# 4G.net
KiCad netlist of a schematic drawn in Altium Designer
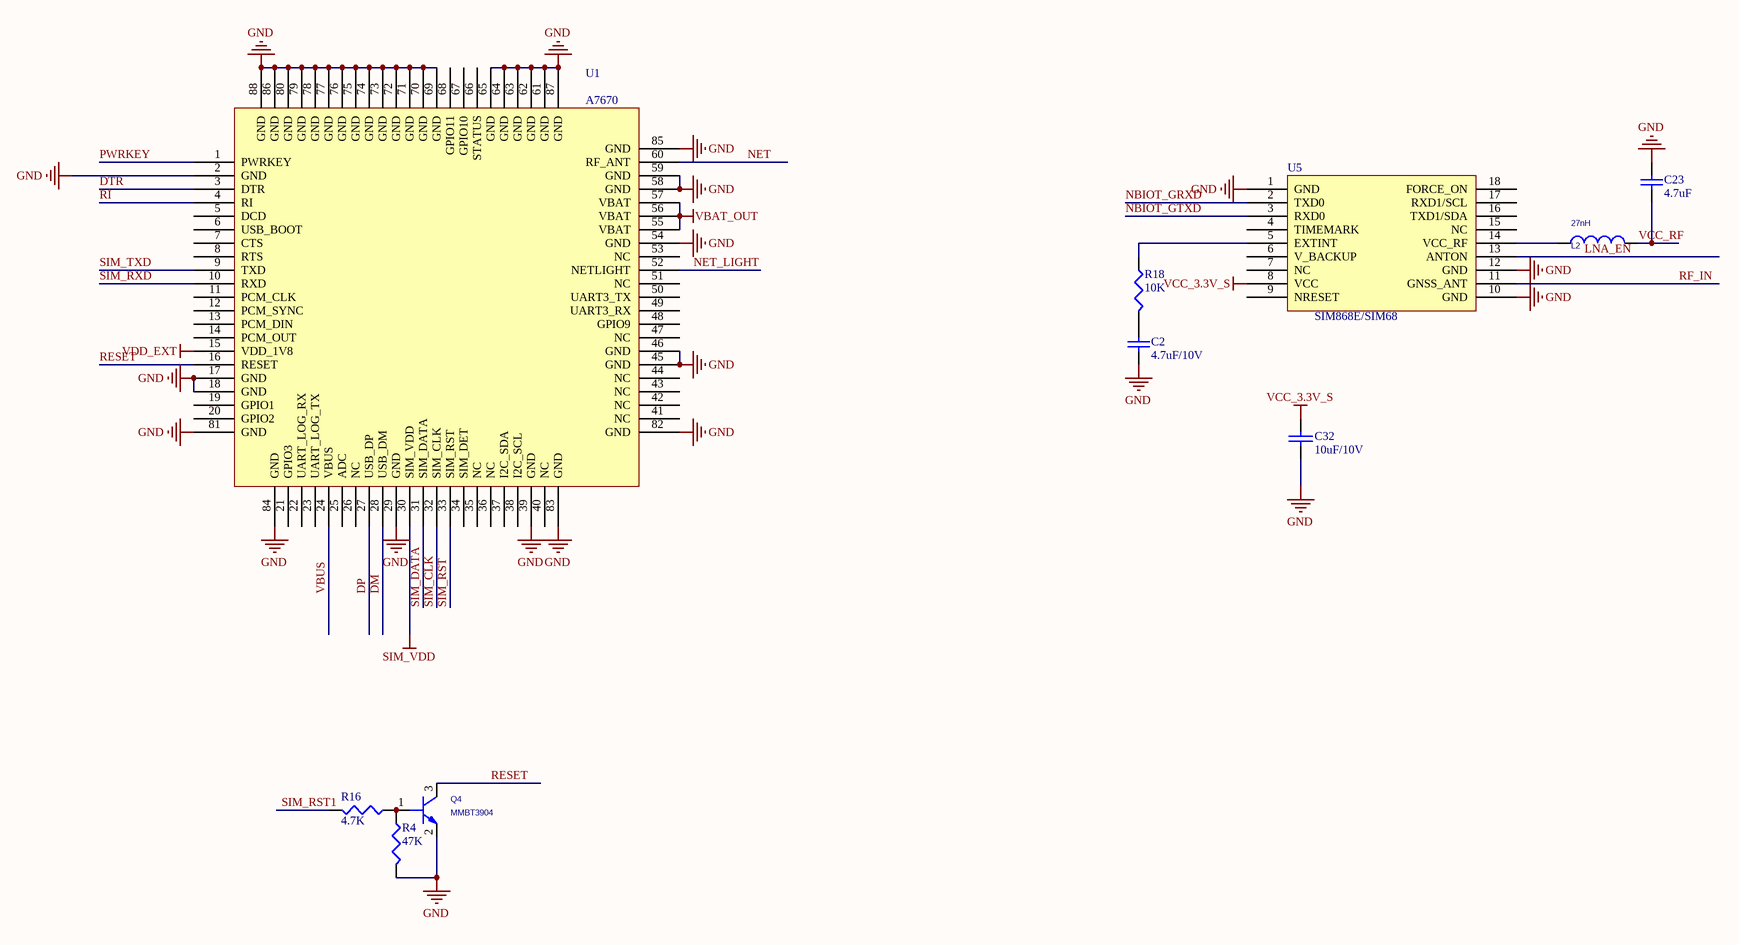
[diagram p0: 4G.SchDoc]

(export (version "E")
  (design (tool "Eeschema 10.0.6"))
  (components
    (comp (ref "C2")
      (value "4.7uF/10V")
      (footprint "0402c")
      (description "Capacitor")
      (fields (field (name "PUBLISHER") "Altium Limited"))
      (libsource (lib "Miscellaneous Devices") (part "Cap"))
    )
    (comp (ref "C23")
      (value "4.7uF")
      (footprint "0402c")
      (description "Capacitor")
      (fields (field (name "PUBLISHER") "Altium Limited"))
      (libsource (lib "Miscellaneous Devices") (part "Cap"))
    )
    (comp (ref "C32")
      (value "10uF/10V")
      (footprint "0402C")
      (description "Capacitor")
      (libsource (lib "ZWLIntegrated_Library") (part "CAP"))
    )
    (comp (ref "L2") (value "27nH") (footprint "0402R") (libsource (lib "*") (part "INDUCTOR_1")))
    (comp (ref "Q4") (value "MMBT3904") (footprint "SOT23-3") (libsource (lib "*") (part "2N1069_1")))
    (comp (ref "R4")
      (value "47K")
      (footprint "0402R")
      (libsource (lib "ZWLIntegrated_Library") (part "RES1"))
    )
    (comp (ref "R16")
      (value "4.7K")
      (footprint "0402R")
      (libsource (lib "ZWLIntegrated_Library") (part "RES1"))
    )
    (comp (ref "R18")
      (value "10K")
      (footprint "0402R")
      (libsource (lib "ZWLIntegrated_Library") (part "RES1"))
    )
    (comp (ref "U1") (value "A7670") (footprint "A7670") (libsource (lib "stm32") (part "A7670")))
    (comp (ref "U5") (value "SIM868E/SIM68") (footprint "SIM68MB") (libsource (lib "stm32") (part "SIM68MB")))
  )
  (nets
    (net (code "1") (name "/DM") (class "Default")
      (node (ref "U1") (pin "28") (pinfunction "USB_DM_28") (pintype "passive"))
    )
    (net (code "2") (name "/DP") (class "Default")
      (node (ref "U1") (pin "27") (pinfunction "USB_DP_27") (pintype "passive"))
    )
    (net (code "3") (name "/DTR") (class "Default")
      (node (ref "U1") (pin "3") (pinfunction "DTR_3") (pintype "passive"))
    )
    (net (code "4") (name "/LNA_EN") (class "Default")
      (node (ref "U5") (pin "13") (pinfunction "ANTON_13") (pintype "passive"))
    )
    (net (code "5") (name "/NBIOT_GRXD") (class "Default")
      (node (ref "U5") (pin "2") (pinfunction "TXD0_2") (pintype "passive"))
    )
    (net (code "6") (name "/NBIOT_GTXD") (class "Default")
      (node (ref "U5") (pin "3") (pinfunction "RXD0_3") (pintype "passive"))
    )
    (net (code "7") (name "/NET") (class "Default")
      (node (ref "U1") (pin "60") (pinfunction "RF_ANT_60") (pintype "passive"))
    )
    (net (code "8") (name "/NET_LIGHT") (class "Default")
      (node (ref "U1") (pin "52") (pinfunction "NETLIGHT_52") (pintype "passive"))
    )
    (net (code "9") (name "/PWRKEY") (class "Default")
      (node (ref "U1") (pin "1") (pinfunction "PWRKEY_1") (pintype "passive"))
    )
    (net (code "10") (name "/RESET") (class "Default")
      (node (ref "Q4") (pin "3") (pinfunction "C_3") (pintype "passive"))
      (node (ref "U1") (pin "16") (pinfunction "RESET_16") (pintype "passive"))
    )
    (net (code "11") (name "/RF_IN") (class "Default")
      (node (ref "U5") (pin "11") (pinfunction "GNSS_ANT_11") (pintype "passive"))
    )
    (net (code "12") (name "/RI") (class "Default")
      (node (ref "U1") (pin "4") (pinfunction "RI_4") (pintype "passive"))
    )
    (net (code "13") (name "/SIM_CLK") (class "Default")
      (node (ref "U1") (pin "32") (pinfunction "SIM_CLK_32") (pintype "passive"))
    )
    (net (code "14") (name "/SIM_DATA") (class "Default")
      (node (ref "U1") (pin "31") (pinfunction "SIM_DATA_31") (pintype "passive"))
    )
    (net (code "15") (name "/SIM_RST") (class "Default")
      (node (ref "U1") (pin "33") (pinfunction "SIM_RST_33") (pintype "passive"))
    )
    (net (code "16") (name "/SIM_RST1") (class "Default")
      (node (ref "R16") (pin "2") (pinfunction "2_2") (pintype "passive"))
    )
    (net (code "17") (name "/SIM_RXD") (class "Default")
      (node (ref "U1") (pin "10") (pinfunction "RXD_10") (pintype "passive"))
    )
    (net (code "18") (name "/SIM_TXD") (class "Default")
      (node (ref "U1") (pin "9") (pinfunction "TXD_9") (pintype "passive"))
    )
    (net (code "19") (name "/VBUS") (class "Default")
      (node (ref "U1") (pin "24") (pinfunction "VBUS_24") (pintype "passive"))
    )
    (net (code "20") (name "/VCC_RF") (class "Default")
      (node (ref "C23") (pin "2") (pinfunction "2_2") (pintype "passive"))
      (node (ref "L2") (pin "2") (pinfunction "2_2") (pintype "passive"))
    )
    (net (code "21") (name "GND") (class "Default")
      (node (ref "C2") (pin "1") (pinfunction "1_1") (pintype "passive"))
      (node (ref "C23") (pin "1") (pinfunction "1_1") (pintype "passive"))
      (node (ref "C32") (pin "1") (pinfunction "1_1") (pintype "passive"))
      (node (ref "Q4") (pin "2") (pinfunction "E_2") (pintype "passive"))
      (node (ref "R4") (pin "2") (pinfunction "2_2") (pintype "passive"))
      (node (ref "U1") (pin "17") (pinfunction "GND_17") (pintype "passive"))
      (node (ref "U1") (pin "18") (pinfunction "GND_18") (pintype "passive"))
      (node (ref "U1") (pin "2") (pinfunction "GND_2") (pintype "passive"))
      (node (ref "U1") (pin "29") (pinfunction "GND_29") (pintype "passive"))
      (node (ref "U1") (pin "39") (pinfunction "GND_39") (pintype "passive"))
      (node (ref "U1") (pin "45") (pinfunction "GND_45") (pintype "passive"))
      (node (ref "U1") (pin "46") (pinfunction "GND_46") (pintype "passive"))
      (node (ref "U1") (pin "54") (pinfunction "GND_54") (pintype "passive"))
      (node (ref "U1") (pin "58") (pinfunction "GND_58") (pintype "passive"))
      (node (ref "U1") (pin "59") (pinfunction "GND_59") (pintype "passive"))
      (node (ref "U1") (pin "61") (pinfunction "GND_61") (pintype "passive"))
      (node (ref "U1") (pin "62") (pinfunction "GND_62") (pintype "passive"))
      (node (ref "U1") (pin "63") (pinfunction "GND_63") (pintype "passive"))
      (node (ref "U1") (pin "64") (pinfunction "GND_64") (pintype "passive"))
      (node (ref "U1") (pin "65") (pinfunction "GND_65") (pintype "passive"))
      (node (ref "U1") (pin "69") (pinfunction "GND_69") (pintype "passive"))
      (node (ref "U1") (pin "70") (pinfunction "GND_70") (pintype "passive"))
      (node (ref "U1") (pin "71") (pinfunction "GND_71") (pintype "passive"))
      (node (ref "U1") (pin "72") (pinfunction "GND_72") (pintype "passive"))
      (node (ref "U1") (pin "73") (pinfunction "GND_73") (pintype "passive"))
      (node (ref "U1") (pin "74") (pinfunction "GND_74") (pintype "passive"))
      (node (ref "U1") (pin "75") (pinfunction "GND_75") (pintype "passive"))
      (node (ref "U1") (pin "76") (pinfunction "GND_76") (pintype "passive"))
      (node (ref "U1") (pin "77") (pinfunction "GND_77") (pintype "passive"))
      (node (ref "U1") (pin "78") (pinfunction "GND_78") (pintype "passive"))
      (node (ref "U1") (pin "79") (pinfunction "GND_79") (pintype "passive"))
      (node (ref "U1") (pin "80") (pinfunction "GND_80") (pintype "passive"))
      (node (ref "U1") (pin "81") (pinfunction "GND_81") (pintype "passive"))
      (node (ref "U1") (pin "82") (pinfunction "GND_82") (pintype "passive"))
      (node (ref "U1") (pin "83") (pinfunction "GND_83") (pintype "passive"))
      (node (ref "U1") (pin "84") (pinfunction "GND_84") (pintype "passive"))
      (node (ref "U1") (pin "85") (pinfunction "GND_85") (pintype "passive"))
      (node (ref "U1") (pin "86") (pinfunction "GND_86") (pintype "passive"))
      (node (ref "U1") (pin "87") (pinfunction "GND_87") (pintype "passive"))
      (node (ref "U1") (pin "88") (pinfunction "GND_88") (pintype "passive"))
      (node (ref "U5") (pin "1") (pinfunction "GND_1") (pintype "passive"))
      (node (ref "U5") (pin "10") (pinfunction "GND_10") (pintype "passive"))
      (node (ref "U5") (pin "12") (pinfunction "GND_12") (pintype "passive"))
    )
    (net (code "22") (name "Net-(C2-Pad2)") (class "Default")
      (node (ref "C2") (pin "2") (pinfunction "2_2") (pintype "passive"))
      (node (ref "R18") (pin "2") (pinfunction "2_2") (pintype "passive"))
    )
    (net (code "23") (name "Net-(Q4-B)") (class "Default")
      (node (ref "Q4") (pin "1") (pinfunction "B_1") (pintype "passive"))
      (node (ref "R16") (pin "1") (pinfunction "1_1") (pintype "passive"))
      (node (ref "R4") (pin "1") (pinfunction "1_1") (pintype "passive"))
    )
    (net (code "24") (name "Net-(U5-EXTINT)") (class "Default")
      (node (ref "R18") (pin "1") (pinfunction "1_1") (pintype "passive"))
      (node (ref "U5") (pin "5") (pinfunction "EXTINT_5") (pintype "passive"))
    )
    (net (code "25") (name "Net-(U5-VCC_RF)") (class "Default")
      (node (ref "L2") (pin "1") (pinfunction "1_1") (pintype "passive"))
      (node (ref "U5") (pin "14") (pinfunction "VCC_RF_14") (pintype "passive"))
    )
    (net (code "26") (name "SIM_VDD") (class "Default")
      (node (ref "U1") (pin "30") (pinfunction "SIM_VDD_30") (pintype "passive"))
    )
    (net (code "27") (name "VBAT_OUT") (class "Default")
      (node (ref "U1") (pin "55") (pinfunction "VBAT_55") (pintype "passive"))
      (node (ref "U1") (pin "56") (pinfunction "VBAT_56") (pintype "passive"))
      (node (ref "U1") (pin "57") (pinfunction "VBAT_57") (pintype "passive"))
    )
    (net (code "28") (name "VCC_3.3V_S") (class "Default")
      (node (ref "C32") (pin "2") (pinfunction "2_2") (pintype "passive"))
      (node (ref "U5") (pin "8") (pinfunction "VCC_8") (pintype "passive"))
    )
    (net (code "29") (name "VDD_EXT") (class "Default")
      (node (ref "U1") (pin "15") (pinfunction "VDD_1V8_15") (pintype "passive"))
    )
    (net (code "30") (name "unconnected-(U1-ADC-Pad25)") (class "Default")
      (node (ref "U1") (pin "25") (pinfunction "ADC_25") (pintype "passive"))
    )
    (net (code "31") (name "unconnected-(U1-CTS-Pad7)") (class "Default")
      (node (ref "U1") (pin "7") (pinfunction "CTS_7") (pintype "passive"))
    )
    (net (code "32") (name "unconnected-(U1-DCD-Pad5)") (class "Default")
      (node (ref "U1") (pin "5") (pinfunction "DCD_5") (pintype "passive"))
    )
    (net (code "33") (name "unconnected-(U1-GPIO1-Pad19)") (class "Default")
      (node (ref "U1") (pin "19") (pinfunction "GPIO1_19") (pintype "passive"))
    )
    (net (code "34") (name "unconnected-(U1-GPIO2-Pad20)") (class "Default")
      (node (ref "U1") (pin "20") (pinfunction "GPIO2_20") (pintype "passive"))
    )
    (net (code "35") (name "unconnected-(U1-GPIO3-Pad21)") (class "Default")
      (node (ref "U1") (pin "21") (pinfunction "GPIO3_21") (pintype "passive"))
    )
    (net (code "36") (name "unconnected-(U1-GPIO9-Pad48)") (class "Default")
      (node (ref "U1") (pin "48") (pinfunction "GPIO9_48") (pintype "passive"))
    )
    (net (code "37") (name "unconnected-(U1-GPIO10-Pad67)") (class "Default")
      (node (ref "U1") (pin "67") (pinfunction "GPIO10_67") (pintype "passive"))
    )
    (net (code "38") (name "unconnected-(U1-GPIO11-Pad68)") (class "Default")
      (node (ref "U1") (pin "68") (pinfunction "GPIO11_68") (pintype "passive"))
    )
    (net (code "39") (name "unconnected-(U1-I2C_SCL-Pad38)") (class "Default")
      (node (ref "U1") (pin "38") (pinfunction "I2C_SCL_38") (pintype "passive"))
    )
    (net (code "40") (name "unconnected-(U1-I2C_SDA-Pad37)") (class "Default")
      (node (ref "U1") (pin "37") (pinfunction "I2C_SDA_37") (pintype "passive"))
    )
    (net (code "41") (name "unconnected-(U1-NC-Pad26)") (class "Default")
      (node (ref "U1") (pin "26") (pinfunction "NC_26") (pintype "passive"))
    )
    (net (code "42") (name "unconnected-(U1-NC-Pad35)") (class "Default")
      (node (ref "U1") (pin "35") (pinfunction "NC_35") (pintype "passive"))
    )
    (net (code "43") (name "unconnected-(U1-NC-Pad36)") (class "Default")
      (node (ref "U1") (pin "36") (pinfunction "NC_36") (pintype "passive"))
    )
    (net (code "44") (name "unconnected-(U1-NC-Pad40)") (class "Default")
      (node (ref "U1") (pin "40") (pinfunction "NC_40") (pintype "passive"))
    )
    (net (code "45") (name "unconnected-(U1-NC-Pad41)") (class "Default")
      (node (ref "U1") (pin "41") (pinfunction "NC_41") (pintype "passive"))
    )
    (net (code "46") (name "unconnected-(U1-NC-Pad42)") (class "Default")
      (node (ref "U1") (pin "42") (pinfunction "NC_42") (pintype "passive"))
    )
    (net (code "47") (name "unconnected-(U1-NC-Pad43)") (class "Default")
      (node (ref "U1") (pin "43") (pinfunction "NC_43") (pintype "passive"))
    )
    (net (code "48") (name "unconnected-(U1-NC-Pad44)") (class "Default")
      (node (ref "U1") (pin "44") (pinfunction "NC_44") (pintype "passive"))
    )
    (net (code "49") (name "unconnected-(U1-NC-Pad47)") (class "Default")
      (node (ref "U1") (pin "47") (pinfunction "NC_47") (pintype "passive"))
    )
    (net (code "50") (name "unconnected-(U1-NC-Pad51)") (class "Default")
      (node (ref "U1") (pin "51") (pinfunction "NC_51") (pintype "passive"))
    )
    (net (code "51") (name "unconnected-(U1-NC-Pad53)") (class "Default")
      (node (ref "U1") (pin "53") (pinfunction "NC_53") (pintype "passive"))
    )
    (net (code "52") (name "unconnected-(U1-PCM_CLK-Pad11)") (class "Default")
      (node (ref "U1") (pin "11") (pinfunction "PCM_CLK_11") (pintype "passive"))
    )
    (net (code "53") (name "unconnected-(U1-PCM_DIN-Pad13)") (class "Default")
      (node (ref "U1") (pin "13") (pinfunction "PCM_DIN_13") (pintype "passive"))
    )
    (net (code "54") (name "unconnected-(U1-PCM_OUT-Pad14)") (class "Default")
      (node (ref "U1") (pin "14") (pinfunction "PCM_OUT_14") (pintype "passive"))
    )
    (net (code "55") (name "unconnected-(U1-PCM_SYNC-Pad12)") (class "Default")
      (node (ref "U1") (pin "12") (pinfunction "PCM_SYNC_12") (pintype "passive"))
    )
    (net (code "56") (name "unconnected-(U1-RTS-Pad8)") (class "Default")
      (node (ref "U1") (pin "8") (pinfunction "RTS_8") (pintype "passive"))
    )
    (net (code "57") (name "unconnected-(U1-SIM_DET-Pad34)") (class "Default")
      (node (ref "U1") (pin "34") (pinfunction "SIM_DET_34") (pintype "passive"))
    )
    (net (code "58") (name "unconnected-(U1-STATUS-Pad66)") (class "Default")
      (node (ref "U1") (pin "66") (pinfunction "STATUS_66") (pintype "passive"))
    )
    (net (code "59") (name "unconnected-(U1-UART3_RX-Pad49)") (class "Default")
      (node (ref "U1") (pin "49") (pinfunction "UART3_RX_49") (pintype "passive"))
    )
    (net (code "60") (name "unconnected-(U1-UART3_TX-Pad50)") (class "Default")
      (node (ref "U1") (pin "50") (pinfunction "UART3_TX_50") (pintype "passive"))
    )
    (net (code "61") (name "unconnected-(U1-UART_LOG_RX-Pad22)") (class "Default")
      (node (ref "U1") (pin "22") (pinfunction "UART_LOG_RX_22") (pintype "passive"))
    )
    (net (code "62") (name "unconnected-(U1-UART_LOG_TX-Pad23)") (class "Default")
      (node (ref "U1") (pin "23") (pinfunction "UART_LOG_TX_23") (pintype "passive"))
    )
    (net (code "63") (name "unconnected-(U1-USB_BOOT-Pad6)") (class "Default")
      (node (ref "U1") (pin "6") (pinfunction "USB_BOOT_6") (pintype "passive"))
    )
    (net (code "64") (name "unconnected-(U5-FORCE_ON-Pad18)") (class "Default")
      (node (ref "U5") (pin "18") (pinfunction "FORCE_ON_18") (pintype "passive"))
    )
    (net (code "65") (name "unconnected-(U5-NC-Pad7)") (class "Default")
      (node (ref "U5") (pin "7") (pinfunction "NC_7") (pintype "passive"))
    )
    (net (code "66") (name "unconnected-(U5-NC-Pad15)") (class "Default")
      (node (ref "U5") (pin "15") (pinfunction "NC_15") (pintype "passive"))
    )
    (net (code "67") (name "unconnected-(U5-NRESET-Pad9)") (class "Default")
      (node (ref "U5") (pin "9") (pinfunction "NRESET_9") (pintype "passive"))
    )
    (net (code "68") (name "unconnected-(U5-RXD1{slash}SCL-Pad17)") (class "Default")
      (node (ref "U5") (pin "17") (pinfunction "RXD1/SCL_17") (pintype "passive"))
    )
    (net (code "69") (name "unconnected-(U5-TIMEMARK-Pad4)") (class "Default")
      (node (ref "U5") (pin "4") (pinfunction "TIMEMARK_4") (pintype "passive"))
    )
    (net (code "70") (name "unconnected-(U5-TXD1{slash}SDA-Pad16)") (class "Default")
      (node (ref "U5") (pin "16") (pinfunction "TXD1/SDA_16") (pintype "passive"))
    )
    (net (code "71") (name "unconnected-(U5-V_BACKUP-Pad6)") (class "Default")
      (node (ref "U5") (pin "6") (pinfunction "V_BACKUP_6") (pintype "passive"))
    )
  )
)
